# newIMU.net
KiCad netlist of a schematic drawn in Altium Designer
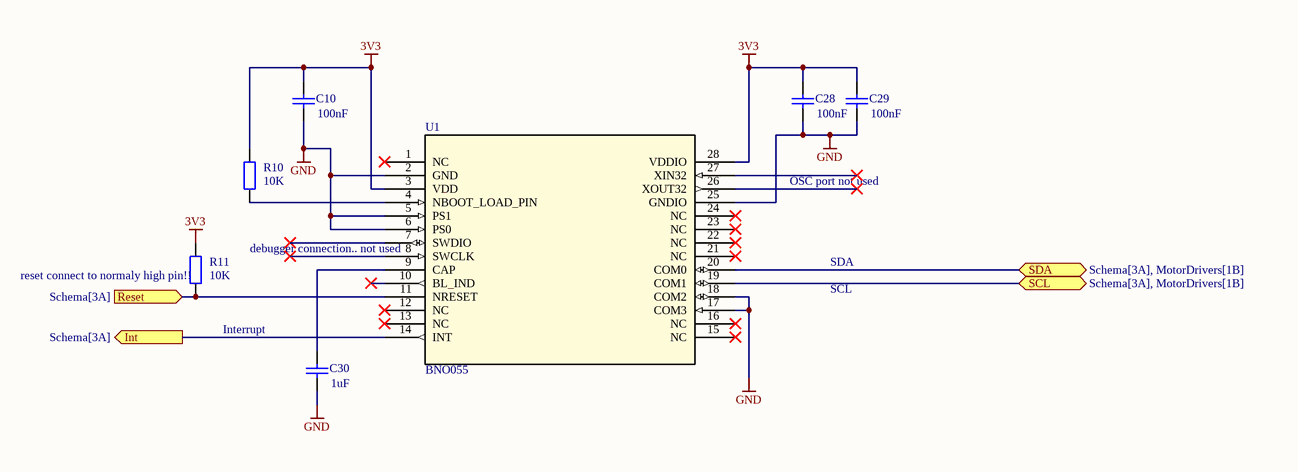
[diagram p0: newIMU.SchDoc]

(export (version "E")
  (design (tool "Eeschema 10.0.6"))
  (components
    (comp (ref "C10")
      (value "100nF")
      (footprint "0805_Lorin")
      (description "Capacitor")
      (fields (field (name "Comment") "Cap") (field (name "PUBLISHER") "Altium Limited"))
      (libsource (lib "Miscellaneous Devices") (part "Cap"))
    )
    (comp (ref "C28")
      (value "100nF")
      (footprint "0805_Lorin")
      (description "Capacitor")
      (fields (field (name "Comment") "Cap") (field (name "PUBLISHER") "Altium Limited"))
      (libsource (lib "Miscellaneous Devices") (part "Cap"))
    )
    (comp (ref "C29")
      (value "100nF")
      (footprint "0805_Lorin")
      (description "Capacitor")
      (fields (field (name "Comment") "Cap") (field (name "PUBLISHER") "Altium Limited"))
      (libsource (lib "Miscellaneous Devices") (part "Cap"))
    )
    (comp (ref "C30")
      (value "1uF")
      (footprint "0805_Lorin")
      (description "Capacitor")
      (fields (field (name "Comment") "Cap") (field (name "PUBLISHER") "Altium Limited"))
      (libsource (lib "Miscellaneous Devices") (part "Cap"))
    )
    (comp (ref "R10")
      (value "10K")
      (footprint "0805_Lorin")
      (description "Resistor")
      (fields (field (name "Comment") "Res2") (field (name "PUBLISHER") "Altium Limited"))
      (libsource (lib "Miscellaneous Devices") (part "Res2"))
    )
    (comp (ref "R11")
      (value "10K")
      (footprint "0805_Lorin")
      (description "Resistor")
      (fields (field (name "Comment") "Res2") (field (name "PUBLISHER") "Altium Limited"))
      (libsource (lib "Miscellaneous Devices") (part "Res2"))
    )
    (comp (ref "U1")
      (value "BNO055")
      (footprint "QFN_BNO055_BOS")
      (description "No Description Available")
      (fields (field (name "COPYRIGHT") "Copyright (C) 2024 Ultra Librarian. All rights reserved."))
      (libsource (lib "SchematicLib") (part "BNO055"))
    )
  )
  (nets
    (net (code "1") (name "/Int") (class "Default")
      (node (ref "U1") (pin "14") (pinfunction "INT_14") (pintype "output"))
    )
    (net (code "2") (name "/Reset") (class "Default")
      (node (ref "R11") (pin "1") (pinfunction "1_1") (pintype "passive"))
      (node (ref "U1") (pin "11") (pinfunction "NRESET_11") (pintype "passive"))
    )
    (net (code "3") (name "/SCL") (class "Default")
      (node (ref "U1") (pin "19") (pinfunction "COM1_19") (pintype "bidirectional"))
    )
    (net (code "4") (name "/SDA") (class "Default")
      (node (ref "U1") (pin "20") (pinfunction "COM0_20") (pintype "bidirectional"))
    )
    (net (code "5") (name "3V3") (class "Default")
      (node (ref "C10") (pin "2") (pinfunction "2_2") (pintype "passive"))
      (node (ref "C28") (pin "2") (pinfunction "2_2") (pintype "passive"))
      (node (ref "C29") (pin "2") (pinfunction "2_2") (pintype "passive"))
      (node (ref "R10") (pin "2") (pinfunction "2_2") (pintype "passive"))
      (node (ref "R11") (pin "2") (pinfunction "2_2") (pintype "passive"))
      (node (ref "U1") (pin "28") (pinfunction "VDDIO_28") (pintype "power_in"))
      (node (ref "U1") (pin "3") (pinfunction "VDD_3") (pintype "power_in"))
    )
    (net (code "6") (name "GND") (class "Default")
      (node (ref "C10") (pin "1") (pinfunction "1_1") (pintype "passive"))
      (node (ref "C28") (pin "1") (pinfunction "1_1") (pintype "passive"))
      (node (ref "C29") (pin "1") (pinfunction "1_1") (pintype "passive"))
      (node (ref "C30") (pin "1") (pinfunction "1_1") (pintype "passive"))
      (node (ref "U1") (pin "17") (pinfunction "COM3_17") (pintype "input"))
      (node (ref "U1") (pin "18") (pinfunction "COM2_18") (pintype "bidirectional"))
      (node (ref "U1") (pin "2") (pinfunction "GND_2") (pintype "power_in"))
      (node (ref "U1") (pin "25") (pinfunction "GNDIO_25") (pintype "power_in"))
      (node (ref "U1") (pin "5") (pinfunction "PS1_5") (pintype "input"))
      (node (ref "U1") (pin "6") (pinfunction "PS0_6") (pintype "input"))
    )
    (net (code "7") (name "Net-(U1-CAP)") (class "Default")
      (node (ref "C30") (pin "2") (pinfunction "2_2") (pintype "passive"))
      (node (ref "U1") (pin "9") (pinfunction "CAP_9") (pintype "passive"))
    )
    (net (code "8") (name "Net-(U1-NBOOT_LOAD_PIN)") (class "Default")
      (node (ref "R10") (pin "1") (pinfunction "1_1") (pintype "passive"))
      (node (ref "U1") (pin "4") (pinfunction "NBOOT_LOAD_PIN_4") (pintype "input"))
    )
    (net (code "9") (name "unconnected-(U1-BL_IND-Pad10)") (class "Default")
      (node (ref "U1") (pin "10") (pinfunction "BL_IND_10") (pintype "output+no_connect"))
    )
    (net (code "10") (name "unconnected-(U1-NC-Pad1)") (class "Default")
      (node (ref "U1") (pin "1") (pinfunction "NC_1") (pintype "passive+no_connect"))
    )
    (net (code "11") (name "unconnected-(U1-NC-Pad12)") (class "Default")
      (node (ref "U1") (pin "12") (pinfunction "NC_12") (pintype "passive+no_connect"))
    )
    (net (code "12") (name "unconnected-(U1-NC-Pad13)") (class "Default")
      (node (ref "U1") (pin "13") (pinfunction "NC_13") (pintype "passive+no_connect"))
    )
    (net (code "13") (name "unconnected-(U1-NC-Pad15)") (class "Default")
      (node (ref "U1") (pin "15") (pinfunction "NC_15") (pintype "passive+no_connect"))
    )
    (net (code "14") (name "unconnected-(U1-NC-Pad16)") (class "Default")
      (node (ref "U1") (pin "16") (pinfunction "NC_16") (pintype "passive+no_connect"))
    )
    (net (code "15") (name "unconnected-(U1-NC-Pad21)") (class "Default")
      (node (ref "U1") (pin "21") (pinfunction "NC_21") (pintype "passive+no_connect"))
    )
    (net (code "16") (name "unconnected-(U1-NC-Pad22)") (class "Default")
      (node (ref "U1") (pin "22") (pinfunction "NC_22") (pintype "passive+no_connect"))
    )
    (net (code "17") (name "unconnected-(U1-NC-Pad23)") (class "Default")
      (node (ref "U1") (pin "23") (pinfunction "NC_23") (pintype "passive+no_connect"))
    )
    (net (code "18") (name "unconnected-(U1-NC-Pad24)") (class "Default")
      (node (ref "U1") (pin "24") (pinfunction "NC_24") (pintype "passive+no_connect"))
    )
    (net (code "19") (name "unconnected-(U1-SWCLK-Pad8)") (class "Default")
      (node (ref "U1") (pin "8") (pinfunction "SWCLK_8") (pintype "input+no_connect"))
    )
    (net (code "20") (name "unconnected-(U1-SWDIO-Pad7)") (class "Default")
      (node (ref "U1") (pin "7") (pinfunction "SWDIO_7") (pintype "bidirectional+no_connect"))
    )
    (net (code "21") (name "unconnected-(U1-XIN32-Pad27)") (class "Default")
      (node (ref "U1") (pin "27") (pinfunction "XIN32_27") (pintype "input+no_connect"))
    )
    (net (code "22") (name "unconnected-(U1-XOUT32-Pad26)") (class "Default")
      (node (ref "U1") (pin "26") (pinfunction "XOUT32_26") (pintype "output+no_connect"))
    )
  )
)
